# Qwiic-CO2_Sensor-SCD40.net
KiCad netlist of a schematic drawn in EAGLE
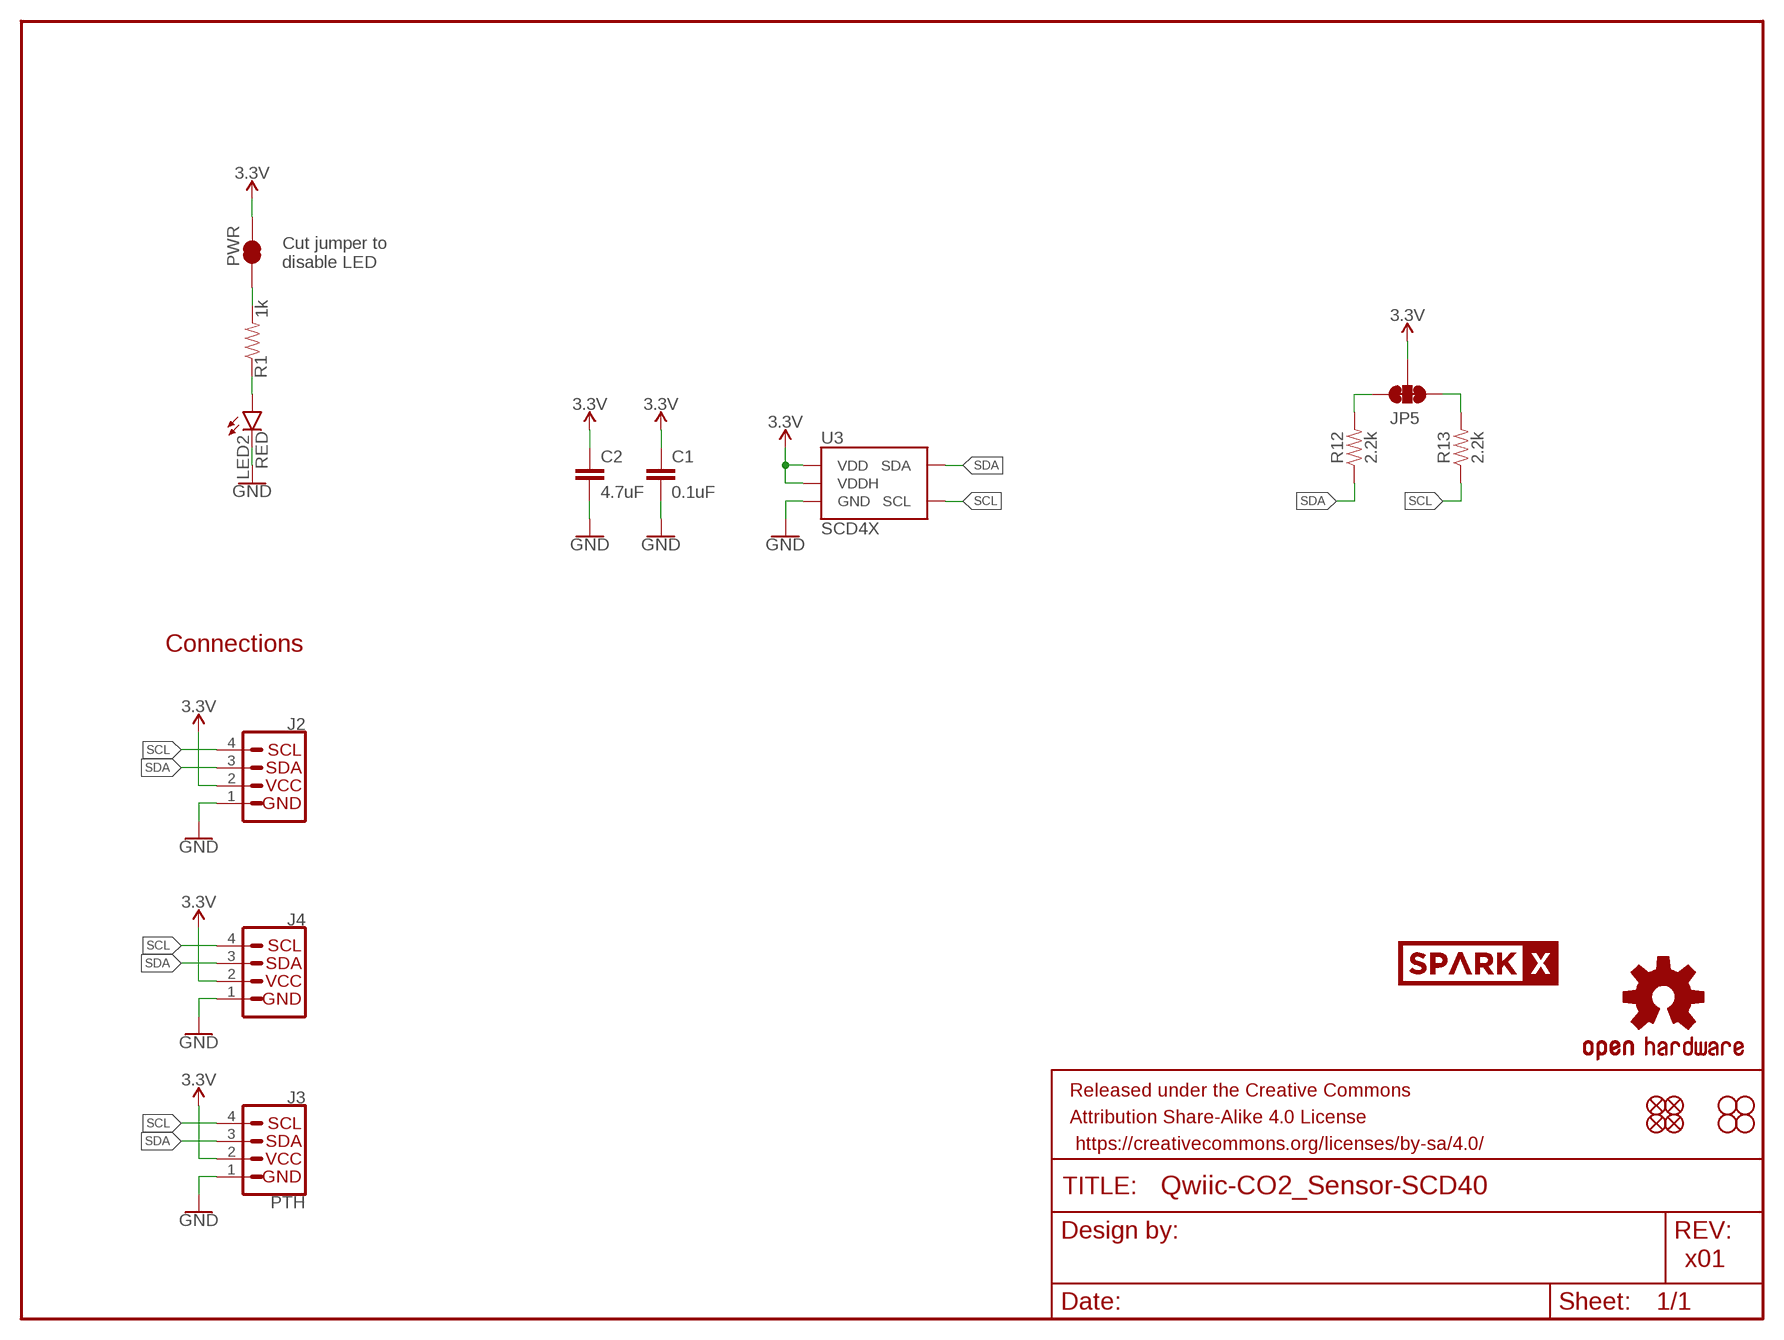
[diagram p0: schematic, sheet 1]

(export (version "E")
  (design (tool "Eeschema 10.0.6"))
  (components
    (comp (ref "C1")
      (value "0.1uF")
      (footprint "eagle-import:0603")
      (libsource (lib "eagle-import") (part "0.1UF-0603-25V-(+80/-20%)"))
    )
    (comp (ref "C2")
      (value "4.7uF")
      (footprint "eagle-import:0603")
      (libsource (lib "eagle-import") (part "4.7UF-0603-6.3V-(10%)"))
    )
    (comp (ref "FRAME1")
      (value "FRAME-LETTER")
      (footprint "eagle-import:CREATIVE_COMMONS")
      (libsource (lib "eagle-import") (part "FRAME-LETTER"))
    )
    (comp (ref "J2")
      (value "Qwiic Right Angle")
      (footprint "eagle-import:JST04_1MM_RA")
      (libsource (lib "eagle-import") (part "I2C_STANDARDQWIIC"))
    )
    (comp (ref "J3")
      (value "PTH")
      (footprint "eagle-import:1X04_NO_SILK")
      (libsource (lib "eagle-import") (part "SparkX_I2C_STANDARD_NO_SILK"))
    )
    (comp (ref "J4")
      (value "Qwiic Right Angle")
      (footprint "eagle-import:JST04_1MM_RA")
      (libsource (lib "eagle-import") (part "I2C_STANDARDQWIIC"))
    )
    (comp (ref "JP5")
      (value "JUMPER-SMT_3_2-NC_TRACE_SILK")
      (footprint "eagle-import:SMT-JUMPER_3_2-NC_TRACE_SILK")
      (libsource (lib "eagle-import") (part "JUMPER-SMT_3_2-NC_TRACE_SILK"))
    )
    (comp (ref "JP21")
      (value "FIDUCIALUFIDUCIAL")
      (footprint "eagle-import:MICRO-FIDUCIAL")
      (libsource (lib "eagle-import") (part "FIDUCIALUFIDUCIAL"))
    )
    (comp (ref "JP31")
      (value "STAND-OFF")
      (footprint "eagle-import:STAND-OFF")
      (libsource (lib "eagle-import") (part "STAND-OFF"))
    )
    (comp (ref "JP41")
      (value "STAND-OFF")
      (footprint "eagle-import:STAND-OFF")
      (libsource (lib "eagle-import") (part "STAND-OFF"))
    )
    (comp (ref "JP61")
      (value "FIDUCIALUFIDUCIAL")
      (footprint "eagle-import:MICRO-FIDUCIAL")
      (libsource (lib "eagle-import") (part "FIDUCIALUFIDUCIAL"))
    )
    (comp (ref "JP71")
      (value "FIDUCIALUFIDUCIAL")
      (footprint "eagle-import:MICRO-FIDUCIAL")
      (libsource (lib "eagle-import") (part "FIDUCIALUFIDUCIAL"))
    )
    (comp (ref "JP81")
      (value "FIDUCIALUFIDUCIAL")
      (footprint "eagle-import:MICRO-FIDUCIAL")
      (libsource (lib "eagle-import") (part "FIDUCIALUFIDUCIAL"))
    )
    (comp (ref "JP91")
      (value "STAND-OFF")
      (footprint "eagle-import:STAND-OFF")
      (libsource (lib "eagle-import") (part "STAND-OFF"))
    )
    (comp (ref "JP101")
      (value "STAND-OFF")
      (footprint "eagle-import:STAND-OFF")
      (libsource (lib "eagle-import") (part "STAND-OFF"))
    )
    (comp (ref "LED2")
      (value "RED")
      (footprint "eagle-import:LED-0603")
      (libsource (lib "eagle-import") (part "LED-RED0603"))
    )
    (comp (ref "LOGO1")
      (value "OSHW-LOGOMINI")
      (footprint "eagle-import:OSHW-LOGO-MINI")
      (libsource (lib "eagle-import") (part "OSHW-LOGOMINI"))
    )
    (comp (ref "PWR")
      (value "JUMPER-SMT_2_NC_TRACE_SILK")
      (footprint "eagle-import:SMT-JUMPER_2_NC_TRACE_SILK")
      (libsource (lib "eagle-import") (part "JUMPER-SMT_2_NC_TRACE_SILK"))
    )
    (comp (ref "R1")
      (value "1k")
      (footprint "eagle-import:0603")
      (libsource (lib "eagle-import") (part "1KOHM-0603-1/10W-1%"))
    )
    (comp (ref "R12")
      (value "2.2k")
      (footprint "eagle-import:0603")
      (libsource (lib "eagle-import") (part "2.2KOHM-0603-1/10W-1%"))
    )
    (comp (ref "R13")
      (value "2.2k")
      (footprint "eagle-import:0603")
      (libsource (lib "eagle-import") (part "2.2KOHM-0603-1/10W-1%"))
    )
    (comp (ref "U$5")
      (value "SPARKX-LOGO4")
      (footprint "eagle-import:SPARKX-MEDIUM")
      (libsource (lib "eagle-import") (part "SPARKX-LOGO4"))
    )
    (comp (ref "U3")
      (value "SCD4X")
      (footprint "eagle-import:SCD4X")
      (libsource (lib "eagle-import") (part "SCD4X"))
    )
  )
  (nets
    (net (code "1") (name "3.3V") (class "Default")
      (node (ref "C1") (pin "1") (pinfunction "1_1") (pintype "passive"))
      (node (ref "C2") (pin "1") (pinfunction "1_1") (pintype "passive"))
      (node (ref "J2") (pin "2") (pinfunction "2_2") (pintype "power_in"))
      (node (ref "J3") (pin "2") (pinfunction "VCC_2") (pintype "power_in"))
      (node (ref "J4") (pin "2") (pinfunction "2_2") (pintype "power_in"))
      (node (ref "JP5") (pin "2") (pinfunction "2_2") (pintype "passive"))
      (node (ref "PWR") (pin "2") (pinfunction "2_2") (pintype "passive"))
      (node (ref "U3") (pin "19") (pinfunction "VDDH_19") (pintype "power_in"))
      (node (ref "U3") (pin "7") (pinfunction "VDD_7") (pintype "power_in"))
    )
    (net (code "2") (name "GND") (class "Default")
      (node (ref "C1") (pin "2") (pinfunction "2_2") (pintype "passive"))
      (node (ref "C2") (pin "2") (pinfunction "2_2") (pintype "passive"))
      (node (ref "J2") (pin "1") (pinfunction "1_1") (pintype "power_in"))
      (node (ref "J3") (pin "1") (pinfunction "GND_1") (pintype "power_in"))
      (node (ref "J4") (pin "1") (pinfunction "1_1") (pintype "power_in"))
      (node (ref "LED2") (pin "C") (pinfunction "C_C") (pintype "passive"))
      (node (ref "U3") (pin "20") (pinfunction "GND_20") (pintype "power_in"))
      (node (ref "U3") (pin "6") (pinfunction "GND_6") (pintype "power_in"))
      (node (ref "U3") (pin "CP") (pinfunction "GND_CP") (pintype "power_in"))
    )
    (net (code "3") (name "Net-(JP5-Pad1)") (class "Default")
      (node (ref "JP5") (pin "1") (pinfunction "1_1") (pintype "passive"))
      (node (ref "R13") (pin "2") (pinfunction "2_2") (pintype "passive"))
    )
    (net (code "4") (name "Net-(JP5-Pad3)") (class "Default")
      (node (ref "JP5") (pin "3") (pinfunction "3_3") (pintype "passive"))
      (node (ref "R12") (pin "2") (pinfunction "2_2") (pintype "passive"))
    )
    (net (code "5") (name "Net-(LED2-PadA)") (class "Default")
      (node (ref "LED2") (pin "A") (pinfunction "A_A") (pintype "passive"))
      (node (ref "R1") (pin "1") (pinfunction "1_1") (pintype "passive"))
    )
    (net (code "6") (name "Net-(PWR-Pad1)") (class "Default")
      (node (ref "PWR") (pin "1") (pinfunction "1_1") (pintype "passive"))
      (node (ref "R1") (pin "2") (pinfunction "2_2") (pintype "passive"))
    )
    (net (code "7") (name "SCL") (class "Default")
      (node (ref "J2") (pin "4") (pinfunction "4_4") (pintype "passive"))
      (node (ref "J3") (pin "4") (pinfunction "SCL_4") (pintype "passive"))
      (node (ref "J4") (pin "4") (pinfunction "4_4") (pintype "passive"))
      (node (ref "R13") (pin "1") (pinfunction "1_1") (pintype "passive"))
      (node (ref "U3") (pin "9") (pinfunction "SCL_9") (pintype "bidirectional"))
    )
    (net (code "8") (name "SDA") (class "Default")
      (node (ref "J2") (pin "3") (pinfunction "3_3") (pintype "passive"))
      (node (ref "J3") (pin "3") (pinfunction "SDA_3") (pintype "passive"))
      (node (ref "J4") (pin "3") (pinfunction "3_3") (pintype "passive"))
      (node (ref "R12") (pin "1") (pinfunction "1_1") (pintype "passive"))
      (node (ref "U3") (pin "10") (pinfunction "SDA_10") (pintype "bidirectional"))
    )
  )
)
